# Controller_2_3_Atmega2560.net
KiCad netlist of a schematic drawn in EAGLE
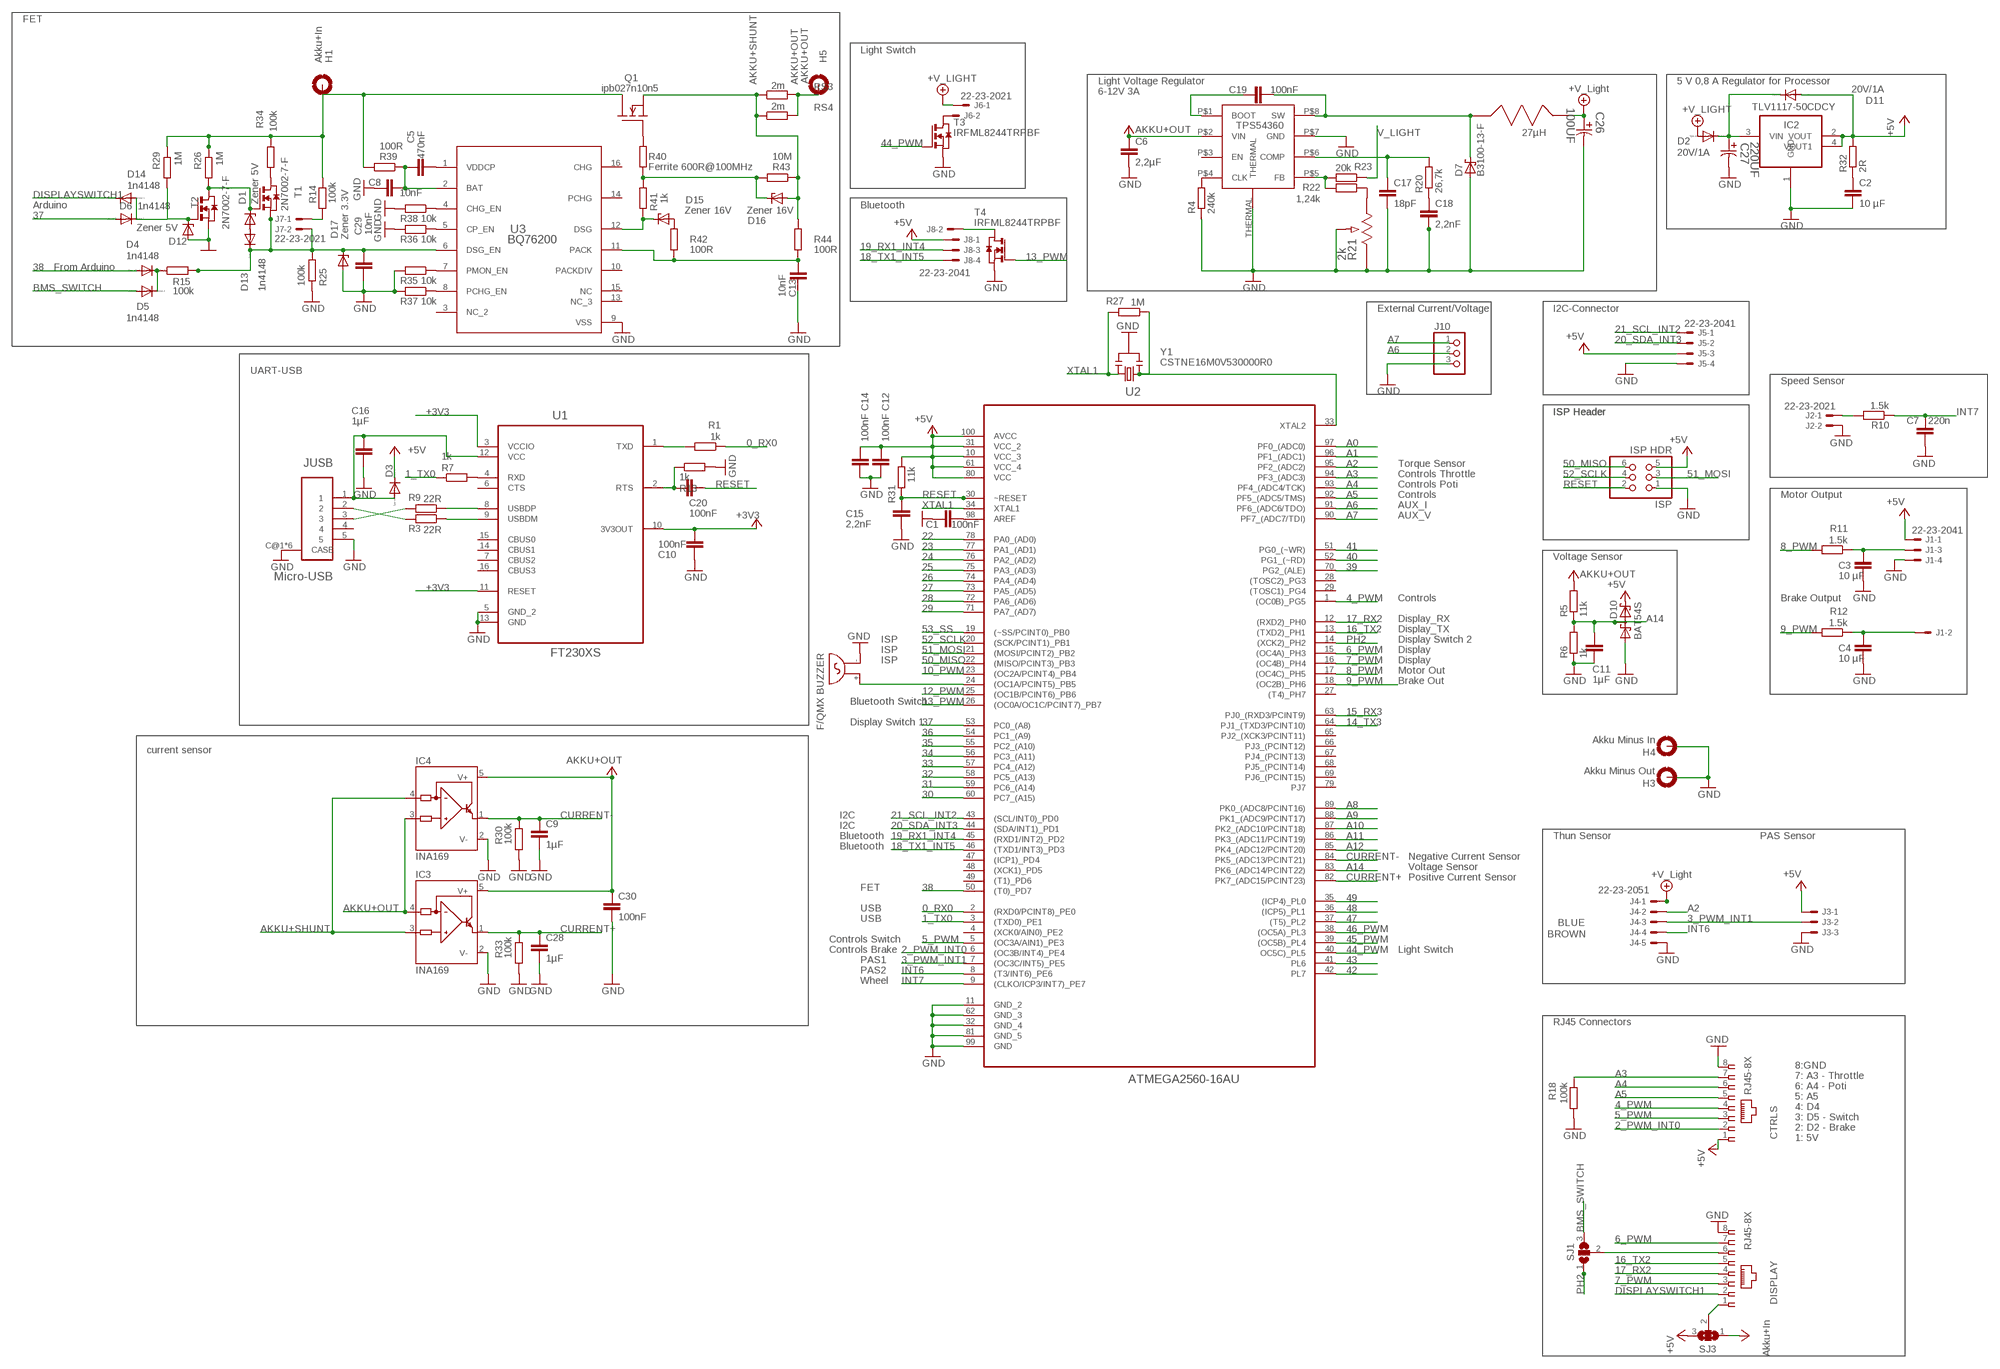
[diagram p0: schematic, sheet 1]

(export (version "E")
  (design (tool "Eeschema 10.0.6"))
  (components
    (comp (ref "BUZZER")
      (value "F/QMX")
      (footprint "eagle-import:F_QMX")
      (libsource (lib "eagle-import") (part "F/QMX"))
    )
    (comp (ref "C1")
      (value "100nF")
      (footprint "eagle-import:C0603")
      (libsource (lib "eagle-import") (part "C-EUC0603"))
    )
    (comp (ref "C2")
      (value "10 µF")
      (footprint "eagle-import:C1206")
      (libsource (lib "eagle-import") (part "C-EUC1206"))
    )
    (comp (ref "C3")
      (value "10 µF")
      (footprint "eagle-import:C1206")
      (libsource (lib "eagle-import") (part "C-EUC1206"))
    )
    (comp (ref "C4")
      (value "10 µF")
      (footprint "eagle-import:C1206")
      (libsource (lib "eagle-import") (part "C-EUC1206"))
    )
    (comp (ref "C5")
      (value "470nF")
      (footprint "eagle-import:C0603")
      (libsource (lib "eagle-import") (part "C-EUC0603"))
    )
    (comp (ref "C6")
      (value "2,2µF")
      (footprint "eagle-import:C1210")
      (libsource (lib "eagle-import") (part "C-EUC1210"))
    )
    (comp (ref "C7")
      (value "220n")
      (footprint "eagle-import:C0603")
      (libsource (lib "eagle-import") (part "C-EUC0603"))
    )
    (comp (ref "C8")
      (value "10nF")
      (footprint "eagle-import:C0603")
      (libsource (lib "eagle-import") (part "C-EUC0603"))
    )
    (comp (ref "C9")
      (value "1µF")
      (footprint "eagle-import:C0603")
      (libsource (lib "eagle-import") (part "C-EUC0603"))
    )
    (comp (ref "C10")
      (value "100nF")
      (footprint "eagle-import:C0603")
      (libsource (lib "eagle-import") (part "C-EUC0603"))
    )
    (comp (ref "C11")
      (value "1µF")
      (footprint "eagle-import:C0603")
      (libsource (lib "eagle-import") (part "C-EUC0603"))
    )
    (comp (ref "C12")
      (value "100nF")
      (footprint "eagle-import:C0603")
      (libsource (lib "eagle-import") (part "C-EUC0603"))
    )
    (comp (ref "C13")
      (value "10nF")
      (footprint "eagle-import:C0603")
      (libsource (lib "eagle-import") (part "C-EUC0603"))
    )
    (comp (ref "C14")
      (value "100nF")
      (footprint "eagle-import:C0603")
      (libsource (lib "eagle-import") (part "C-EUC0603"))
    )
    (comp (ref "C15")
      (value "2,2nF")
      (footprint "eagle-import:C0603")
      (libsource (lib "eagle-import") (part "C-EUC0603"))
    )
    (comp (ref "C16")
      (value "1µF")
      (footprint "eagle-import:C0603")
      (libsource (lib "eagle-import") (part "C-EUC0603"))
    )
    (comp (ref "C17")
      (value "18pF")
      (footprint "eagle-import:C0603")
      (libsource (lib "eagle-import") (part "C-EUC0603"))
    )
    (comp (ref "C18")
      (value "2,2nF")
      (footprint "eagle-import:C0603")
      (libsource (lib "eagle-import") (part "C-EUC0603"))
    )
    (comp (ref "C19")
      (value "100nF")
      (footprint "eagle-import:C0603")
      (libsource (lib "eagle-import") (part "C-EUC0603"))
    )
    (comp (ref "C20")
      (value "100nF")
      (footprint "eagle-import:C0603")
      (libsource (lib "eagle-import") (part "C-EUC0603"))
    )
    (comp (ref "C26")
      (value "100UF")
      (footprint "eagle-import:CAPAE660X800N")
      (fields (field (name "MPN") "EEE-FPE101XAP") (field (name "TOLERANCE") "±20 %"))
      (libsource (lib "eagle-import") (part "EEE--CASE-D8FPE101XAP"))
    )
    (comp (ref "C27")
      (value "220UF")
      (footprint "eagle-import:CAPAE660X800N")
      (fields (field (name "MPN") "EEE-FPC221XAP") (field (name "TOLERANCE") "±20 %"))
      (libsource (lib "eagle-import") (part "EEE--CASE-D8FPC221XAP"))
    )
    (comp (ref "C28")
      (value "1µF")
      (footprint "eagle-import:C0603")
      (libsource (lib "eagle-import") (part "C-EUC0603"))
    )
    (comp (ref "C29")
      (value "10nF")
      (footprint "eagle-import:C0603")
      (libsource (lib "eagle-import") (part "C-EUC0603"))
    )
    (comp (ref "C30")
      (value "100nF")
      (footprint "eagle-import:C0603")
      (libsource (lib "eagle-import") (part "C-EUC0603"))
    )
    (comp (ref "CTRLS")
      (value "RJ45-8X")
      (footprint "eagle-import:RJ45-NO-SHIELD")
      (libsource (lib "eagle-import") (part "RJ45-8X"))
    )
    (comp (ref "D1")
      (value "Zener 5V")
      (footprint "eagle-import:SOD323-W")
      (libsource (lib "eagle-import") (part "ZENER-DIODESOD323-W"))
    )
    (comp (ref "D2")
      (value "20V/1A")
      (footprint "eagle-import:DO-214AC")
      (libsource (lib "eagle-import") (part "DIODE-DO-214AC"))
    )
    (comp (ref "D3")
      (value "20V/1A")
      (footprint "eagle-import:DO-214AC")
      (libsource (lib "eagle-import") (part "DIODE-DO-214AC"))
    )
    (comp (ref "D4")
      (value "1n4148")
      (footprint "eagle-import:SOD323-W")
      (libsource (lib "eagle-import") (part "DIODE-SOD323-W"))
    )
    (comp (ref "D5")
      (value "1n4148")
      (footprint "eagle-import:SOD323-W")
      (libsource (lib "eagle-import") (part "DIODE-SOD323-W"))
    )
    (comp (ref "D6")
      (value "1n4148")
      (footprint "eagle-import:SOD323-W")
      (libsource (lib "eagle-import") (part "DIODE-SOD323-W"))
    )
    (comp (ref "D7")
      (value "B3100-13-F")
      (footprint "eagle-import:SMC")
      (libsource (lib "eagle-import") (part "SCHOTTKY-DIODESMC"))
    )
    (comp (ref "D10")
      (value "BAT54S")
      (footprint "eagle-import:SOT23")
      (libsource (lib "eagle-import") (part "BAT54S"))
    )
    (comp (ref "D11")
      (value "20V/1A")
      (footprint "eagle-import:DO-214AC")
      (libsource (lib "eagle-import") (part "DIODE-DO-214AC"))
    )
    (comp (ref "D12")
      (value "Zener 5V")
      (footprint "eagle-import:SOD323-W")
      (libsource (lib "eagle-import") (part "ZENER-DIODESOD323-W"))
    )
    (comp (ref "D13")
      (value "1n4148")
      (footprint "eagle-import:SOD323-W")
      (libsource (lib "eagle-import") (part "DIODE-SOD323-W"))
    )
    (comp (ref "D14")
      (value "1n4148")
      (footprint "eagle-import:SOD323-W")
      (libsource (lib "eagle-import") (part "DIODE-SOD323-W"))
    )
    (comp (ref "D15")
      (value "Zener 16V")
      (footprint "eagle-import:SOD323-W")
      (libsource (lib "eagle-import") (part "ZENER-DIODESOD323-W"))
    )
    (comp (ref "D16")
      (value "Zener 16V")
      (footprint "eagle-import:SOD323-W")
      (libsource (lib "eagle-import") (part "ZENER-DIODESOD323-W"))
    )
    (comp (ref "D17")
      (value "Zener 3.3V")
      (footprint "eagle-import:SOD323-W")
      (libsource (lib "eagle-import") (part "ZENER-DIODESOD323-W"))
    )
    (comp (ref "DISPLAY")
      (value "RJ45-8X")
      (footprint "eagle-import:RJ45-NO-SHIELD")
      (libsource (lib "eagle-import") (part "RJ45-8X"))
    )
    (comp (ref "H1")
      (value "Akku+In")
      (footprint "eagle-import:2,8-PAD")
      (libsource (lib "eagle-import") (part "MOUNT-PAD-ROUND2.8"))
    )
    (comp (ref "H3")
      (value "Akku Minus Out")
      (footprint "eagle-import:2,8-PAD")
      (libsource (lib "eagle-import") (part "MOUNT-PAD-ROUND2.8"))
    )
    (comp (ref "H4")
      (value "Akku Minus In")
      (footprint "eagle-import:2,8-PAD")
      (libsource (lib "eagle-import") (part "MOUNT-PAD-ROUND2.8"))
    )
    (comp (ref "H5")
      (value "AKKU+OUT")
      (footprint "eagle-import:2,8-PAD")
      (libsource (lib "eagle-import") (part "MOUNT-PAD-ROUND2.8"))
    )
    (comp (ref "IC2")
      (value "TLV1117-50CDCY")
      (footprint "eagle-import:SOT223")
      (fields (field (name "MPN") "REG1117"))
      (libsource (lib "eagle-import") (part "REG1117"))
    )
    (comp (ref "IC3")
      (value "INA169")
      (footprint "eagle-import:SOT23-5")
      (fields (field (name "MF") "TEXAS INSTRUMENTS") (field (name "MPN") "INA168NA/250"))
      (libsource (lib "eagle-import") (part "INA168"))
    )
    (comp (ref "IC4")
      (value "INA169")
      (footprint "eagle-import:SOT23-5")
      (fields (field (name "MF") "TEXAS INSTRUMENTS") (field (name "MPN") "INA168NA/250"))
      (libsource (lib "eagle-import") (part "INA168"))
    )
    (comp (ref "ISP")
      (value "ISP HDR")
      (footprint "eagle-import:2X03")
      (libsource (lib "eagle-import") (part "PINHD-2X3"))
    )
    (comp (ref "J1")
      (value "22-23-2041")
      (footprint "eagle-import:22-23-2041")
      (fields
        (field (name "MF") "MOLEX")
        (field (name "MPN") "22-23-2041")
        (field (name "OC_FARNELL") "1462920")
        (field (name "OC_NEWARK") "38C0355")
      )
      (libsource (lib "eagle-import") (part "22-23-2041"))
    )
    (comp (ref "J2")
      (value "22-23-2021")
      (footprint "eagle-import:22-23-2021")
      (fields (field (name "MF") "MOLEX"))
      (libsource (lib "eagle-import") (part "22-23-2021"))
    )
    (comp (ref "J3")
      (value "22-23-2031")
      (footprint "eagle-import:22-23-2031")
      (fields (field (name "MF") "MOLEX"))
      (libsource (lib "eagle-import") (part "22-23-2031"))
    )
    (comp (ref "J4")
      (value "22-23-2051")
      (footprint "eagle-import:22-23-2051")
      (fields (field (name "MF") "MOLEX"))
      (libsource (lib "eagle-import") (part "22-23-2051"))
    )
    (comp (ref "J5")
      (value "22-23-2041")
      (footprint "eagle-import:22-23-2041")
      (fields (field (name "MF") "MOLEX"))
      (libsource (lib "eagle-import") (part "22-23-2041"))
    )
    (comp (ref "J6")
      (value "22-23-2021")
      (footprint "eagle-import:22-23-2021")
      (fields
        (field (name "MF") "MOLEX")
        (field (name "MF_1") "MOLEX")
        (field (name "MPN") "22-23-2021")
        (field (name "OC_FARNELL") "1462926")
        (field (name "OC_NEWARK") "25C3832")
      )
      (libsource (lib "eagle-import") (part "22-23-2021"))
    )
    (comp (ref "J7")
      (value "22-23-2021")
      (footprint "eagle-import:22-23-2021")
      (fields (field (name "MF") "MOLEX"))
      (libsource (lib "eagle-import") (part "22-23-2021"))
    )
    (comp (ref "J8")
      (value "22-23-2041")
      (footprint "eagle-import:22-23-2041")
      (fields (field (name "MF") "MOLEX"))
      (libsource (lib "eagle-import") (part "22-23-2041"))
    )
    (comp (ref "J10")
      (value "PINHD-1X3")
      (footprint "eagle-import:1X03")
      (libsource (lib "eagle-import") (part "PINHD-1X3"))
    )
    (comp (ref "JUSB")
      (value "Micro-USB")
      (footprint "eagle-import:MOLEX_47346-0001")
      (fields (field (name "MPN") "47346-0001"))
      (libsource (lib "eagle-import") (part "47346-0001"))
    )
    (comp (ref "Q1")
      (value "ipb027n10n5")
      (footprint "eagle-import:D2PAK")
      (libsource (lib "eagle-import") (part "IRF510D2PAK"))
    )
    (comp (ref "R1")
      (value "1k")
      (footprint "eagle-import:R0603")
      (libsource (lib "eagle-import") (part "R-EU_R0603"))
    )
    (comp (ref "R3")
      (value "22R")
      (footprint "eagle-import:R0603")
      (libsource (lib "eagle-import") (part "R-EU_R0603"))
    )
    (comp (ref "R4")
      (value "240k")
      (footprint "eagle-import:R0603")
      (libsource (lib "eagle-import") (part "R-EU_R0603"))
    )
    (comp (ref "R5")
      (value "11k")
      (footprint "eagle-import:R0603")
      (libsource (lib "eagle-import") (part "resistor_R-EU_R0603"))
    )
    (comp (ref "R6")
      (value "1k")
      (footprint "eagle-import:R0603")
      (libsource (lib "eagle-import") (part "resistor_R-EU_R0603"))
    )
    (comp (ref "R7")
      (value "1k")
      (footprint "eagle-import:R0603")
      (libsource (lib "eagle-import") (part "R-EU_R0603"))
    )
    (comp (ref "R9")
      (value "22R")
      (footprint "eagle-import:R0603")
      (libsource (lib "eagle-import") (part "R-EU_R0603"))
    )
    (comp (ref "R10")
      (value "1.5k")
      (footprint "eagle-import:R0603")
      (libsource (lib "eagle-import") (part "R-EU_R0603"))
    )
    (comp (ref "R11")
      (value "1.5k")
      (footprint "eagle-import:R0603")
      (libsource (lib "eagle-import") (part "R-EU_R0603"))
    )
    (comp (ref "R12")
      (value "1.5k")
      (footprint "eagle-import:R0603")
      (libsource (lib "eagle-import") (part "R-EU_R0603"))
    )
    (comp (ref "R13")
      (value "1k")
      (footprint "eagle-import:R0603")
      (libsource (lib "eagle-import") (part "R-EU_R0603"))
    )
    (comp (ref "R14")
      (value "100k")
      (footprint "eagle-import:R0603")
      (libsource (lib "eagle-import") (part "R-EU_R0603"))
    )
    (comp (ref "R15")
      (value "100k")
      (footprint "eagle-import:R0603")
      (libsource (lib "eagle-import") (part "R-EU_R0603"))
    )
    (comp (ref "R18")
      (value "100k")
      (footprint "eagle-import:R0603")
      (libsource (lib "eagle-import") (part "R-EU_R0603"))
    )
    (comp (ref "R20")
      (value "26,7k")
      (footprint "eagle-import:R0603")
      (libsource (lib "eagle-import") (part "R-EU_R0603"))
    )
    (comp (ref "R21")
      (value "2k")
      (footprint "eagle-import:POT_EVM3W")
      (fields (field (name "MPN") "EVM3WSX80B23") (field (name "TOLERANCE") "±25 %"))
      (libsource (lib "eagle-import") (part "EVM-3W3WSX80B23"))
    )
    (comp (ref "R22")
      (value "1,24k")
      (footprint "eagle-import:R0603")
      (libsource (lib "eagle-import") (part "R-EU_R0603"))
    )
    (comp (ref "R23")
      (value "20k")
      (footprint "eagle-import:R0603")
      (libsource (lib "eagle-import") (part "R-EU_R0603"))
    )
    (comp (ref "R25")
      (value "100k")
      (footprint "eagle-import:R0603")
      (libsource (lib "eagle-import") (part "R-EU_R0603"))
    )
    (comp (ref "R26")
      (value "1M")
      (footprint "eagle-import:R0603")
      (libsource (lib "eagle-import") (part "R-EU_R0603"))
    )
    (comp (ref "R27")
      (value "1M")
      (footprint "eagle-import:R0603")
      (libsource (lib "eagle-import") (part "resistor_R-EU_R0603"))
    )
    (comp (ref "R29")
      (value "1M")
      (footprint "eagle-import:R0603")
      (libsource (lib "eagle-import") (part "R-EU_R0603"))
    )
    (comp (ref "R30")
      (value "100k")
      (footprint "eagle-import:R0603")
      (libsource (lib "eagle-import") (part "R-EU_R0603"))
    )
    (comp (ref "R31")
      (value "11k")
      (footprint "eagle-import:R0603")
      (libsource (lib "eagle-import") (part "resistor_R-EU_R0603"))
    )
    (comp (ref "R32")
      (value "2R")
      (footprint "eagle-import:R0603")
      (libsource (lib "eagle-import") (part "R-EU_R0603"))
    )
    (comp (ref "R33")
      (value "100k")
      (footprint "eagle-import:R0603")
      (libsource (lib "eagle-import") (part "R-EU_R0603"))
    )
    (comp (ref "R34")
      (value "100k")
      (footprint "eagle-import:R0603")
      (libsource (lib "eagle-import") (part "R-EU_R0603"))
    )
    (comp (ref "R35")
      (value "10k")
      (footprint "eagle-import:R0603")
      (libsource (lib "eagle-import") (part "R-EU_R0603"))
    )
    (comp (ref "R36")
      (value "10k")
      (footprint "eagle-import:R0603")
      (libsource (lib "eagle-import") (part "R-EU_R0603"))
    )
    (comp (ref "R37")
      (value "10k")
      (footprint "eagle-import:R0603")
      (libsource (lib "eagle-import") (part "R-EU_R0603"))
    )
    (comp (ref "R38")
      (value "10k")
      (footprint "eagle-import:R0603")
      (libsource (lib "eagle-import") (part "R-EU_R0603"))
    )
    (comp (ref "R39")
      (value "100R")
      (footprint "eagle-import:R0603")
      (libsource (lib "eagle-import") (part "R-EU_R0603"))
    )
    (comp (ref "R40")
      (value "Ferrite 600R@100MHz")
      (footprint "eagle-import:R0603")
      (libsource (lib "eagle-import") (part "R-EU_R0603"))
    )
    (comp (ref "R41")
      (value "1k")
      (footprint "eagle-import:R0603")
      (libsource (lib "eagle-import") (part "R-EU_R0603"))
    )
    (comp (ref "R42")
      (value "100R")
      (footprint "eagle-import:R0603")
      (libsource (lib "eagle-import") (part "R-EU_R0603"))
    )
    (comp (ref "R43")
      (value "10M")
      (footprint "eagle-import:R0603")
      (libsource (lib "eagle-import") (part "R-EU_R0603"))
    )
    (comp (ref "R44")
      (value "100R")
      (footprint "eagle-import:R0603")
      (libsource (lib "eagle-import") (part "R-EU_R0603"))
    )
    (comp (ref "RS3")
      (value "2m")
      (footprint "eagle-import:R2512")
      (libsource (lib "eagle-import") (part "R-EU_R2512"))
    )
    (comp (ref "RS4")
      (value "2m")
      (footprint "eagle-import:R2512")
      (libsource (lib "eagle-import") (part "R-EU_R2512"))
    )
    (comp (ref "SJ1")
      (value "SJ2W")
      (footprint "eagle-import:SJ_2")
      (libsource (lib "eagle-import") (part "SJ2W"))
    )
    (comp (ref "SJ3")
      (value "SJ2W")
      (footprint "eagle-import:SJ_2")
      (libsource (lib "eagle-import") (part "SJ2W"))
    )
    (comp (ref "T1")
      (value "2N7002-7-F")
      (footprint "eagle-import:SOT-23")
      (libsource (lib "eagle-import") (part "NMOSSOT23"))
    )
    (comp (ref "T2")
      (value "2N7002-7-F")
      (footprint "eagle-import:SOT-23")
      (libsource (lib "eagle-import") (part "NMOSSOT23"))
    )
    (comp (ref "T3")
      (value "IRFML8244TRPBF")
      (footprint "eagle-import:SOT-23")
      (libsource (lib "eagle-import") (part "NMOSSOT23"))
    )
    (comp (ref "T4")
      (value "IRFML8244TRPBF")
      (footprint "eagle-import:SOT-23")
      (libsource (lib "eagle-import") (part "NMOSSOT23"))
    )
    (comp (ref "U1")
      (value "FT230XS")
      (footprint "eagle-import:SOP63P600X175-16N")
      (libsource (lib "eagle-import") (part "FT230XS"))
    )
    (comp (ref "U2")
      (value "ATMEGA2560-16AU")
      (footprint "eagle-import:QFP50P1600X1600X120-100N")
      (libsource (lib "eagle-import") (part "ATMEGA2560-16AU"))
    )
    (comp (ref "U3")
      (value "BQ76200")
      (footprint "eagle-import:PW0016A_N")
      (fields
        (field (name "ALTERNATEPARTNUMBER") "BQ76200PW")
        (field (name "MANUFACTURER") "Texas Instruments")
        (field (name "PARTNUMBER") "BQ76200PWR")
      )
      (libsource (lib "eagle-import") (part "BQ76200PWR"))
    )
    (comp (ref "U9")
      (value "SRR1260-270M")
      (footprint "eagle-import:ARR1260")
      (libsource (lib "eagle-import") (part "SRR1260-270M"))
    )
    (comp (ref "U11")
      (value "TPS54360")
      (footprint "eagle-import:R-PDSO-G8")
      (libsource (lib "eagle-import") (part "TPS54360"))
    )
    (comp (ref "Y1")
      (value "CSTNE16M0V530000R0")
      (footprint "eagle-import:RESONATOR")
      (libsource (lib "eagle-import") (part "RESONATORMU"))
    )
  )
  (nets
    (net (code "1") (name "+3V3") (class "Default")
      (node (ref "C10") (pin "2") (pinfunction "2_2") (pintype "passive"))
      (node (ref "U1") (pin "10") (pinfunction "3V3OUT_10") (pintype "output"))
      (node (ref "U1") (pin "11") (pinfunction "RESET_11") (pintype "input"))
      (node (ref "U1") (pin "3") (pinfunction "VCCIO_3") (pintype "power_in"))
    )
    (net (code "2") (name "+5V") (class "Default")
      (node (ref "C12") (pin "2") (pinfunction "2_2") (pintype "passive"))
      (node (ref "C14") (pin "2") (pinfunction "2_2") (pintype "passive"))
      (node (ref "CTRLS") (pin "1") (pinfunction "1_1") (pintype "passive"))
      (node (ref "D10") (pin "2") (pinfunction "C2_2") (pintype "passive"))
      (node (ref "D11") (pin "A") (pinfunction "A_A") (pintype "passive"))
      (node (ref "D3") (pin "C") (pinfunction "C_C") (pintype "passive"))
      (node (ref "IC2") (pin "2") (pinfunction "VOUT_2") (pintype "output"))
      (node (ref "IC2") (pin "4") (pinfunction "VOUT1_4") (pintype "output"))
      (node (ref "ISP") (pin "5") (pinfunction "5_5") (pintype "passive"))
      (node (ref "J1") (pin "1") (pinfunction "S_1") (pintype "passive"))
      (node (ref "J3") (pin "1") (pinfunction "S_1") (pintype "passive"))
      (node (ref "J5") (pin "3") (pinfunction "S_3") (pintype "passive"))
      (node (ref "J8") (pin "1") (pinfunction "S_1") (pintype "passive"))
      (node (ref "R31") (pin "2") (pinfunction "2_2") (pintype "passive"))
      (node (ref "R32") (pin "2") (pinfunction "2_2") (pintype "passive"))
      (node (ref "SJ3") (pin "3") (pinfunction "3_3") (pintype "passive"))
      (node (ref "U2") (pin "10") (pinfunction "VCC_3_10") (pintype "power_in"))
      (node (ref "U2") (pin "100") (pinfunction "AVCC_100") (pintype "power_in"))
      (node (ref "U2") (pin "31") (pinfunction "VCC_2_31") (pintype "power_in"))
      (node (ref "U2") (pin "61") (pinfunction "VCC_4_61") (pintype "power_in"))
      (node (ref "U2") (pin "80") (pinfunction "VCC_80") (pintype "power_in"))
    )
    (net (code "3") (name "+V_LIGHT") (class "Default")
      (node (ref "C26") (pin "1") (pinfunction "1_1") (pintype "passive"))
      (node (ref "D2") (pin "A") (pinfunction "A_A") (pintype "passive"))
      (node (ref "J4") (pin "1") (pinfunction "S_1") (pintype "passive"))
      (node (ref "J6") (pin "1") (pinfunction "S_1") (pintype "passive"))
      (node (ref "R23") (pin "1") (pinfunction "1_1") (pintype "passive"))
      (node (ref "U9") (pin "P$2") (pinfunction "P$2_P$2") (pintype "bidirectional"))
    )
    (net (code "4") (name "/0_RX0") (class "Default")
      (node (ref "R1") (pin "1") (pinfunction "1_1") (pintype "passive"))
      (node (ref "U2") (pin "2") (pinfunction "(RXD0/PCINT8)_PE0_2") (pintype "bidirectional"))
    )
    (net (code "5") (name "/1_TX0") (class "Default")
      (node (ref "R7") (pin "1") (pinfunction "1_1") (pintype "passive"))
      (node (ref "U2") (pin "3") (pinfunction "(TXD0)_PE1_3") (pintype "bidirectional"))
    )
    (net (code "6") (name "/2_PWM_INT0") (class "Default")
      (node (ref "CTRLS") (pin "2") (pinfunction "2_2") (pintype "passive"))
      (node (ref "U2") (pin "6") (pinfunction "(OC3B/INT4)_PE4_6") (pintype "bidirectional"))
    )
    (net (code "7") (name "/3_PWM_INT1") (class "Default")
      (node (ref "J3") (pin "2") (pinfunction "S_2") (pintype "passive"))
      (node (ref "J4") (pin "3") (pinfunction "S_3") (pintype "passive"))
      (node (ref "U2") (pin "7") (pinfunction "(OC3C/INT5)_PE5_7") (pintype "bidirectional"))
    )
    (net (code "8") (name "/4_PWM") (class "Default")
      (node (ref "CTRLS") (pin "4") (pinfunction "4_4") (pintype "passive"))
      (node (ref "U2") (pin "1") (pinfunction "(OC0B)_PG5_1") (pintype "bidirectional"))
    )
    (net (code "9") (name "/5_PWM") (class "Default")
      (node (ref "CTRLS") (pin "3") (pinfunction "3_3") (pintype "passive"))
      (node (ref "U2") (pin "5") (pinfunction "(OC3A/AIN1)_PE3_5") (pintype "bidirectional"))
    )
    (net (code "10") (name "/6_PWM") (class "Default")
      (node (ref "DISPLAY") (pin "7") (pinfunction "7_7") (pintype "passive"))
      (node (ref "U2") (pin "15") (pinfunction "(OC4A)_PH3_15") (pintype "bidirectional"))
    )
    (net (code "11") (name "/7_PWM") (class "Default")
      (node (ref "DISPLAY") (pin "3") (pinfunction "3_3") (pintype "passive"))
      (node (ref "U2") (pin "16") (pinfunction "(OC4B)_PH4_16") (pintype "bidirectional"))
    )
    (net (code "12") (name "/8_PWM") (class "Default")
      (node (ref "R11") (pin "2") (pinfunction "2_2") (pintype "passive"))
      (node (ref "U2") (pin "17") (pinfunction "(OC4C)_PH5_17") (pintype "bidirectional"))
    )
    (net (code "13") (name "/9_PWM") (class "Default")
      (node (ref "R12") (pin "2") (pinfunction "2_2") (pintype "passive"))
      (node (ref "U2") (pin "18") (pinfunction "(OC2B)_PH6_18") (pintype "bidirectional"))
    )
    (net (code "14") (name "/10_PWM") (class "Default")
      (node (ref "U2") (pin "23") (pinfunction "(OC2A/PCINT4)_PB4_23") (pintype "bidirectional"))
    )
    (net (code "15") (name "/12_PWM") (class "Default")
      (node (ref "U2") (pin "25") (pinfunction "(OC1B/PCINT6)_PB6_25") (pintype "bidirectional"))
    )
    (net (code "16") (name "/13_PWM") (class "Default")
      (node (ref "T4") (pin "3") (pinfunction "G_3") (pintype "passive"))
      (node (ref "U2") (pin "26") (pinfunction "(OC0A/OC1C/PCINT7)_PB7_26") (pintype "bidirectional"))
    )
    (net (code "17") (name "/14_TX3") (class "Default")
      (node (ref "U2") (pin "64") (pinfunction "PJ1_(TXD3/PCINT10)_64") (pintype "bidirectional"))
    )
    (net (code "18") (name "/15_RX3") (class "Default")
      (node (ref "U2") (pin "63") (pinfunction "PJ0_(RXD3/PCINT9)_63") (pintype "bidirectional"))
    )
    (net (code "19") (name "/16_TX2") (class "Default")
      (node (ref "DISPLAY") (pin "5") (pinfunction "5_5") (pintype "passive"))
      (node (ref "U2") (pin "13") (pinfunction "(TXD2)_PH1_13") (pintype "bidirectional"))
    )
    (net (code "20") (name "/17_RX2") (class "Default")
      (node (ref "DISPLAY") (pin "4") (pinfunction "4_4") (pintype "passive"))
      (node (ref "U2") (pin "12") (pinfunction "(RXD2)_PH0_12") (pintype "bidirectional"))
    )
    (net (code "21") (name "/18_TX1_INT5") (class "Default")
      (node (ref "J8") (pin "4") (pinfunction "S_4") (pintype "passive"))
      (node (ref "U2") (pin "46") (pinfunction "(TXD1/INT3)_PD3_46") (pintype "bidirectional"))
    )
    (net (code "22") (name "/19_RX1_INT4") (class "Default")
      (node (ref "J8") (pin "3") (pinfunction "S_3") (pintype "passive"))
      (node (ref "U2") (pin "45") (pinfunction "(RXD1/INT2)_PD2_45") (pintype "bidirectional"))
    )
    (net (code "23") (name "/20_SDA_INT3") (class "Default")
      (node (ref "J5") (pin "2") (pinfunction "S_2") (pintype "passive"))
      (node (ref "U2") (pin "44") (pinfunction "(SDA/INT1)_PD1_44") (pintype "bidirectional"))
    )
    (net (code "24") (name "/21_SCL_INT2") (class "Default")
      (node (ref "J5") (pin "1") (pinfunction "S_1") (pintype "passive"))
      (node (ref "U2") (pin "43") (pinfunction "(SCL/INT0)_PD0_43") (pintype "bidirectional"))
    )
    (net (code "25") (name "/22") (class "Default")
      (node (ref "U2") (pin "78") (pinfunction "PA0_(AD0)_78") (pintype "bidirectional"))
    )
    (net (code "26") (name "/23") (class "Default")
      (node (ref "U2") (pin "77") (pinfunction "PA1_(AD1)_77") (pintype "bidirectional"))
    )
    (net (code "27") (name "/24") (class "Default")
      (node (ref "U2") (pin "76") (pinfunction "PA2_(AD2)_76") (pintype "bidirectional"))
    )
    (net (code "28") (name "/25") (class "Default")
      (node (ref "U2") (pin "75") (pinfunction "PA3_(AD3)_75") (pintype "bidirectional"))
    )
    (net (code "29") (name "/26") (class "Default")
      (node (ref "U2") (pin "74") (pinfunction "PA4_(AD4)_74") (pintype "bidirectional"))
    )
    (net (code "30") (name "/27") (class "Default")
      (node (ref "U2") (pin "73") (pinfunction "PA5_(AD5)_73") (pintype "bidirectional"))
    )
    (net (code "31") (name "/28") (class "Default")
      (node (ref "U2") (pin "72") (pinfunction "PA6_(AD6)_72") (pintype "bidirectional"))
    )
    (net (code "32") (name "/29") (class "Default")
      (node (ref "U2") (pin "71") (pinfunction "PA7_(AD7)_71") (pintype "bidirectional"))
    )
    (net (code "33") (name "/30") (class "Default")
      (node (ref "U2") (pin "60") (pinfunction "PC7_(A15)_60") (pintype "bidirectional"))
    )
    (net (code "34") (name "/31") (class "Default")
      (node (ref "U2") (pin "59") (pinfunction "PC6_(A14)_59") (pintype "bidirectional"))
    )
    (net (code "35") (name "/32") (class "Default")
      (node (ref "U2") (pin "58") (pinfunction "PC5_(A13)_58") (pintype "bidirectional"))
    )
    (net (code "36") (name "/33") (class "Default")
      (node (ref "U2") (pin "57") (pinfunction "PC4_(A12)_57") (pintype "bidirectional"))
    )
    (net (code "37") (name "/34") (class "Default")
      (node (ref "U2") (pin "56") (pinfunction "PC3_(A11)_56") (pintype "bidirectional"))
    )
    (net (code "38") (name "/35") (class "Default")
      (node (ref "U2") (pin "55") (pinfunction "PC2_(A10)_55") (pintype "bidirectional"))
    )
    (net (code "39") (name "/36") (class "Default")
      (node (ref "U2") (pin "54") (pinfunction "PC1_(A9)_54") (pintype "bidirectional"))
    )
    (net (code "40") (name "/37") (class "Default")
      (node (ref "D6") (pin "A") (pinfunction "A_A") (pintype "passive"))
      (node (ref "U2") (pin "53") (pinfunction "PC0_(A8)_53") (pintype "bidirectional"))
    )
    (net (code "41") (name "/38") (class "Default")
      (node (ref "D4") (pin "A") (pinfunction "A_A") (pintype "passive"))
      (node (ref "U2") (pin "50") (pinfunction "(T0)_PD7_50") (pintype "bidirectional"))
    )
    (net (code "42") (name "/39") (class "Default")
      (node (ref "U2") (pin "70") (pinfunction "PG2_(ALE)_70") (pintype "bidirectional"))
    )
    (net (code "43") (name "/40") (class "Default")
      (node (ref "U2") (pin "52") (pinfunction "PG1_(~{RD})_52") (pintype "bidirectional"))
    )
    (net (code "44") (name "/41") (class "Default")
      (node (ref "U2") (pin "51") (pinfunction "PG0_(~{WR})_51") (pintype "bidirectional"))
    )
    (net (code "45") (name "/42") (class "Default")
      (node (ref "U2") (pin "42") (pinfunction "PL7_42") (pintype "bidirectional"))
    )
    (net (code "46") (name "/43") (class "Default")
      (node (ref "U2") (pin "41") (pinfunction "PL6_41") (pintype "bidirectional"))
    )
    (net (code "47") (name "/44_PWM") (class "Default")
      (node (ref "T3") (pin "3") (pinfunction "G_3") (pintype "passive"))
      (node (ref "U2") (pin "40") (pinfunction "OC5C)_PL5_40") (pintype "bidirectional"))
    )
    (net (code "48") (name "/45_PWM") (class "Default")
      (node (ref "U2") (pin "39") (pinfunction "(OC5B)_PL4_39") (pintype "bidirectional"))
    )
    (net (code "49") (name "/46_PWM") (class "Default")
      (node (ref "U2") (pin "38") (pinfunction "(OC5A)_PL3_38") (pintype "bidirectional"))
    )
    (net (code "50") (name "/47") (class "Default")
      (node (ref "U2") (pin "37") (pinfunction "(T5)_PL2_37") (pintype "bidirectional"))
    )
    (net (code "51") (name "/48") (class "Default")
      (node (ref "U2") (pin "36") (pinfunction "(ICP5)_PL1_36") (pintype "bidirectional"))
    )
    (net (code "52") (name "/49") (class "Default")
      (node (ref "U2") (pin "35") (pinfunction "(ICP4)_PL0_35") (pintype "bidirectional"))
    )
    (net (code "53") (name "/50_MISO") (class "Default")
      (node (ref "ISP") (pin "6") (pinfunction "6_6") (pintype "passive"))
      (node (ref "U2") (pin "22") (pinfunction "(MISO/PCINT3)_PB3_22") (pintype "bidirectional"))
    )
    (net (code "54") (name "/51_MOSI") (class "Default")
      (node (ref "ISP") (pin "3") (pinfunction "3_3") (pintype "passive"))
      (node (ref "U2") (pin "21") (pinfunction "(MOSI/PCINT2)_PB2_21") (pintype "bidirectional"))
    )
    (net (code "55") (name "/52_SCLK") (class "Default")
      (node (ref "ISP") (pin "4") (pinfunction "4_4") (pintype "passive"))
      (node (ref "U2") (pin "20") (pinfunction "(SCK/PCINT1)_PB1_20") (pintype "bidirectional"))
    )
    (net (code "56") (name "/53_SS") (class "Default")
      (node (ref "U2") (pin "19") (pinfunction "(~{SS/PCINT0})_PB0_19") (pintype "bidirectional"))
    )
    (net (code "57") (name "/A0") (class "Default")
      (node (ref "U2") (pin "97") (pinfunction "PF0_(ADC0)_97") (pintype "bidirectional"))
    )
    (net (code "58") (name "/A1") (class "Default")
      (node (ref "U2") (pin "96") (pinfunction "PF1_(ADC1)_96") (pintype "bidirectional"))
    )
    (net (code "59") (name "/A2") (class "Default")
      (node (ref "J4") (pin "2") (pinfunction "S_2") (pintype "passive"))
      (node (ref "U2") (pin "95") (pinfunction "PF2_(ADC2)_95") (pintype "bidirectional"))
    )
    (net (code "60") (name "/A3") (class "Default")
      (node (ref "CTRLS") (pin "7") (pinfunction "7_7") (pintype "passive"))
      (node (ref "R18") (pin "1") (pinfunction "1_1") (pintype "passive"))
      (node (ref "U2") (pin "94") (pinfunction "PF3_(ADC3)_94") (pintype "bidirectional"))
    )
    (net (code "61") (name "/A4") (class "Default")
      (node (ref "CTRLS") (pin "6") (pinfunction "6_6") (pintype "passive"))
      (node (ref "U2") (pin "93") (pinfunction "PF4_(ADC4/TCK)_93") (pintype "bidirectional"))
    )
    (net (code "62") (name "/A5") (class "Default")
      (node (ref "CTRLS") (pin "5") (pinfunction "5_5") (pintype "passive"))
      (node (ref "U2") (pin "92") (pinfunction "PF5_(ADC5/TMS)_92") (pintype "bidirectional"))
    )
    (net (code "63") (name "/A6") (class "Default")
      (node (ref "J10") (pin "2") (pinfunction "2_2") (pintype "passive"))
      (node (ref "U2") (pin "91") (pinfunction "PF6_(ADC6/TDO)_91") (pintype "bidirectional"))
    )
    (net (code "64") (name "/A7") (class "Default")
      (node (ref "J10") (pin "1") (pinfunction "1_1") (pintype "passive"))
      (node (ref "U2") (pin "90") (pinfunction "PF7_(ADC7/TDI)_90") (pintype "bidirectional"))
    )
    (net (code "65") (name "/A8") (class "Default")
      (node (ref "U2") (pin "89") (pinfunction "PK0_(ADC8/PCINT16)_89") (pintype "bidirectional"))
    )
    (net (code "66") (name "/A9") (class "Default")
      (node (ref "U2") (pin "88") (pinfunction "PK1_(ADC9/PCINT17)_88") (pintype "bidirectional"))
    )
    (net (code "67") (name "/A10") (class "Default")
      (node (ref "U2") (pin "87") (pinfunction "PK2_(ADC10/PCINT18)_87") (pintype "bidirectional"))
    )
    (net (code "68") (name "/A11") (class "Default")
      (node (ref "U2") (pin "86") (pinfunction "PK3_(ADC11/PCINT19)_86") (pintype "bidirectional"))
    )
    (net (code "69") (name "/A12") (class "Default")
      (node (ref "U2") (pin "85") (pinfunction "PK4_(ADC12/PCINT20)_85") (pintype "bidirectional"))
    )
    (net (code "70") (name "/A14") (class "Default")
      (node (ref "C11") (pin "1") (pinfunction "1_1") (pintype "passive"))
      (node (ref "D10") (pin "3") (pinfunction "C1A2_3") (pintype "passive"))
      (node (ref "R5") (pin "1") (pinfunction "1_1") (pintype "passive"))
      (node (ref "R6") (pin "2") (pinfunction "2_2") (pintype "passive"))
      (node (ref "U2") (pin "83") (pinfunction "PK6_(ADC14/PCINT22)_83") (pintype "bidirectional"))
    )
    (net (code "71") (name "/AKKU+SHUNT") (class "Default")
      (node (ref "D16") (pin "A") (pinfunction "A_A") (pintype "passive"))
      (node (ref "IC3") (pin "3") (pinfunction "IN+_3") (pintype "input"))
      (node (ref "IC4") (pin "4") (pinfunction "IN-_4") (pintype "input"))
      (node (ref "Q1") (pin "3") (pinfunction "S_3") (pintype "passive"))
      (node (ref "R43") (pin "1") (pinfunction "1_1") (pintype "passive"))
      (node (ref "R44") (pin "2") (pinfunction "2_2") (pintype "passive"))
      (node (ref "RS3") (pin "1") (pinfunction "1_1") (pintype "passive"))
      (node (ref "RS4") (pin "1") (pinfunction "1_1") (pintype "passive"))
    )
    (net (code "72") (name "/BMS_SWITCH") (class "Default")
      (node (ref "D5") (pin "A") (pinfunction "A_A") (pintype "passive"))
      (node (ref "SJ1") (pin "3") (pinfunction "3_3") (pintype "passive"))
    )
    (net (code "73") (name "/CURRENT+") (class "Default")
      (node (ref "C28") (pin "1") (pinfunction "1_1") (pintype "passive"))
      (node (ref "IC3") (pin "1") (pinfunction "OUT_1") (pintype "output"))
      (node (ref "R33") (pin "2") (pinfunction "2_2") (pintype "passive"))
      (node (ref "U2") (pin "82") (pinfunction "PK7_(ADC15/PCINT23)_82") (pintype "bidirectional"))
    )
    (net (code "74") (name "/CURRENT-") (class "Default")
      (node (ref "C9") (pin "1") (pinfunction "1_1") (pintype "passive"))
      (node (ref "IC4") (pin "1") (pinfunction "OUT_1") (pintype "output"))
      (node (ref "R30") (pin "2") (pinfunction "2_2") (pintype "passive"))
      (node (ref "U2") (pin "84") (pinfunction "PK5_(ADC13/PCINT21)_84") (pintype "bidirectional"))
    )
    (net (code "75") (name "/DISPLAYSWITCH1") (class "Default")
      (node (ref "D14") (pin "C") (pinfunction "C_C") (pintype "passive"))
      (node (ref "DISPLAY") (pin "2") (pinfunction "2_2") (pintype "passive"))
    )
    (net (code "76") (name "/INT6") (class "Default")
      (node (ref "J4") (pin "4") (pinfunction "S_4") (pintype "passive"))
      (node (ref "U2") (pin "8") (pinfunction "(T3/INT6)_PE6_8") (pintype "bidirectional"))
    )
    (net (code "77") (name "/INT7") (class "Default")
      (node (ref "C7") (pin "1") (pinfunction "1_1") (pintype "passive"))
      (node (ref "R10") (pin "1") (pinfunction "1_1") (pintype "passive"))
      (node (ref "U2") (pin "9") (pinfunction "(CLKO/ICP3/INT7)_PE7_9") (pintype "bidirectional"))
    )
    (net (code "78") (name "/PH2") (class "Default")
      (node (ref "SJ1") (pin "1") (pinfunction "1_1") (pintype "passive"))
      (node (ref "U2") (pin "14") (pinfunction "(XCK2)_PH2_14") (pintype "bidirectional"))
    )
    (net (code "79") (name "/RESET") (class "Default")
      (node (ref "C15") (pin "1") (pinfunction "1_1") (pintype "passive"))
      (node (ref "C20") (pin "2") (pinfunction "2_2") (pintype "passive"))
      (node (ref "ISP") (pin "2") (pinfunction "2_2") (pintype "passive"))
      (node (ref "R31") (pin "1") (pinfunction "1_1") (pintype "passive"))
      (node (ref "U2") (pin "30") (pinfunction "~{RESET}_30") (pintype "input"))
    )
    (net (code "80") (name "/XTAL1") (class "Default")
      (node (ref "R27") (pin "2") (pinfunction "2_2") (pintype "passive"))
      (node (ref "U2") (pin "34") (pinfunction "XTAL1_34") (pintype "input"))
      (node (ref "Y1") (pin "3") (pinfunction "3_3") (pintype "passive"))
    )
    (net (code "81") (name "AKKU+OUT") (class "Default")
      (node (ref "C30") (pin "1") (pinfunction "1_1") (pintype "passive"))
      (node (ref "C6") (pin "1") (pinfunction "1_1") (pintype "passive"))
      (node (ref "H5") (pin "B2,8") (pinfunction "MOUNT_B2,8") (pintype "passive"))
      (node (ref "IC3") (pin "4") (pinfunction "IN-_4") (pintype "input"))
      (node (ref "IC3") (pin "5") (pinfunction "V+_5") (pintype "power_in"))
      (node (ref "IC4") (pin "3") (pinfunction "IN+_3") (pintype "input"))
      (node (ref "IC4") (pin "5") (pinfunction "V+_5") (pintype "power_in"))
      (node (ref "R5") (pin "2") (pinfunction "2_2") (pintype "passive"))
      (node (ref "RS3") (pin "2") (pinfunction "2_2") (pintype "passive"))
      (node (ref "RS4") (pin "2") (pinfunction "2_2") (pintype "passive"))
      (node (ref "U11") (pin "P$2") (pinfunction "VIN_P$2") (pintype "bidirectional"))
    )
    (net (code "82") (name "Akku+In") (class "Default")
      (node (ref "H1") (pin "B2,8") (pinfunction "MOUNT_B2,8") (pintype "passive"))
      (node (ref "Q1") (pin "2") (pinfunction "D_2") (pintype "passive"))
      (node (ref "R14") (pin "2") (pinfunction "2_2") (pintype "passive"))
      (node (ref "R26") (pin "1") (pinfunction "1_1") (pintype "passive"))
      (node (ref "R29") (pin "1") (pinfunction "1_1") (pintype "passive"))
      (node (ref "R34") (pin "1") (pinfunction "1_1") (pintype "passive"))
      (node (ref "R39") (pin "2") (pinfunction "2_2") (pintype "passive"))
      (node (ref "SJ3") (pin "1") (pinfunction "1_1") (pintype "passive"))
    )
    (net (code "83") (name "GND") (class "Default")
      (node (ref "BUZZER") (pin "-") (pinfunction "1_-") (pintype "passive"))
      (node (ref "C1") (pin "2") (pinfunction "2_2") (pintype "passive"))
      (node (ref "C10") (pin "1") (pinfunction "1_1") (pintype "passive"))
      (node (ref "C11") (pin "2") (pinfunction "2_2") (pintype "passive"))
      (node (ref "C12") (pin "1") (pinfunction "1_1") (pintype "passive"))
      (node (ref "C13") (pin "1") (pinfunction "1_1") (pintype "passive"))
      (node (ref "C14") (pin "1") (pinfunction "1_1") (pintype "passive"))
      (node (ref "C15") (pin "2") (pinfunction "2_2") (pintype "passive"))
      (node (ref "C16") (pin "2") (pinfunction "2_2") (pintype "passive"))
      (node (ref "C17") (pin "2") (pinfunction "2_2") (pintype "passive"))
      (node (ref "C18") (pin "2") (pinfunction "2_2") (pintype "passive"))
      (node (ref "C2") (pin "2") (pinfunction "2_2") (pintype "passive"))
      (node (ref "C26") (pin "2") (pinfunction "2_2") (pintype "passive"))
      (node (ref "C27") (pin "2") (pinfunction "2_2") (pintype "passive"))
      (node (ref "C28") (pin "2") (pinfunction "2_2") (pintype "passive"))
      (node (ref "C29") (pin "1") (pinfunction "1_1") (pintype "passive"))
      (node (ref "C3") (pin "2") (pinfunction "2_2") (pintype "passive"))
      (node (ref "C30") (pin "2") (pinfunction "2_2") (pintype "passive"))
      (node (ref "C4") (pin "2") (pinfunction "2_2") (pintype "passive"))
      (node (ref "C6") (pin "2") (pinfunction "2_2") (pintype "passive"))
      (node (ref "C7") (pin "2") (pinfunction "2_2") (pintype "passive"))
      (node (ref "C8") (pin "1") (pinfunction "1_1") (pintype "passive"))
      (node (ref "C9") (pin "2") (pinfunction "2_2") (pintype "passive"))
      (node (ref "CTRLS") (pin "8") (pinfunction "8_8") (pintype "passive"))
      (node (ref "D10") (pin "1") (pinfunction "A1_1") (pintype "passive"))
      (node (ref "D12") (pin "A") (pinfunction "A_A") (pintype "passive"))
      (node (ref "D17") (pin "A") (pinfunction "A_A") (pintype "passive"))
      (node (ref "D7") (pin "A") (pinfunction "A_A") (pintype "passive"))
      (node (ref "DISPLAY") (pin "8") (pinfunction "8_8") (pintype "passive"))
      (node (ref "H3") (pin "B2,8") (pinfunction "MOUNT_B2,8") (pintype "passive"))
      (node (ref "H4") (pin "B2,8") (pinfunction "MOUNT_B2,8") (pintype "passive"))
      (node (ref "IC2") (pin "1") (pinfunction "GND_1") (pintype "power_in"))
      (node (ref "IC3") (pin "2") (pinfunction "V-_2") (pintype "power_in"))
      (node (ref "IC4") (pin "2") (pinfunction "V-_2") (pintype "power_in"))
      (node (ref "ISP") (pin "1") (pinfunction "1_1") (pintype "passive"))
      (node (ref "J1") (pin "4") (pinfunction "S_4") (pintype "passive"))
      (node (ref "J10") (pin "3") (pinfunction "3_3") (pintype "passive"))
      (node (ref "J2") (pin "2") (pinfunction "S_2") (pintype "passive"))
      (node (ref "J3") (pin "3") (pinfunction "S_3") (pintype "passive"))
      (node (ref "J4") (pin "5") (pinfunction "S_5") (pintype "passive"))
      (node (ref "J5") (pin "4") (pinfunction "S_4") (pintype "passive"))
      (node (ref "JUSB") (pin "5") (pinfunction "5_5") (pintype "input"))
      (node (ref "JUSB") (pin "C@1") (pinfunction "CASE_C@1") (pintype "bidirectional"))
      (node (ref "JUSB") (pin "C@2") (pinfunction "CASE_C@2") (pintype "bidirectional"))
      (node (ref "JUSB") (pin "C@3") (pinfunction "CASE_C@3") (pintype "bidirectional"))
      (node (ref "JUSB") (pin "C@4") (pinfunction "CASE_C@4") (pintype "bidirectional"))
      (node (ref "JUSB") (pin "C@5") (pinfunction "CASE_C@5") (pintype "bidirectional"))
      (node (ref "JUSB") (pin "C@6") (pinfunction "CASE_C@6") (pintype "bidirectional"))
      (node (ref "R13") (pin "2") (pinfunction "2_2") (pintype "passive"))
      (node (ref "R18") (pin "2") (pinfunction "2_2") (pintype "passive"))
      (node (ref "R21") (pin "1") (pinfunction "1_1") (pintype "passive"))
      (node (ref "R21") (pin "2") (pinfunction "2_2") (pintype "passive"))
      (node (ref "R25") (pin "1") (pinfunction "1_1") (pintype "passive"))
      (node (ref "R30") (pin "1") (pinfunction "1_1") (pintype "passive"))
      (node (ref "R33") (pin "1") (pinfunction "1_1") (pintype "passive"))
      (node (ref "R35") (pin "2") (pinfunction "2_2") (pintype "passive"))
      (node (ref "R36") (pin "2") (pinfunction "2_2") (pintype "passive"))
      (node (ref "R37") (pin "2") (pinfunction "2_2") (pintype "passive"))
      (node (ref "R38") (pin "2") (pinfunction "2_2") (pintype "passive"))
      (node (ref "R4") (pin "1") (pinfunction "1_1") (pintype "passive"))
      (node (ref "R6") (pin "1") (pinfunction "1_1") (pintype "passive"))
      (node (ref "T2") (pin "2") (pinfunction "S_2") (pintype "passive"))
      (node (ref "T3") (pin "2") (pinfunction "S_2") (pintype "passive"))
      (node (ref "T4") (pin "2") (pinfunction "S_2") (pintype "passive"))
      (node (ref "U1") (pin "13") (pinfunction "GND_13") (pintype "power_in"))
      (node (ref "U1") (pin "5") (pinfunction "GND_2_5") (pintype "power_in"))
      (node (ref "U11") (pin "P$7") (pinfunction "GND_P$7") (pintype "bidirectional"))
      (node (ref "U11") (pin "THERMAL") (pinfunction "THERMAL_THERMAL") (pintype "bidirectional"))
      (node (ref "U2") (pin "11") (pinfunction "GND_2_11") (pintype "passive"))
      (node (ref "U2") (pin "32") (pinfunction "GND_4_32") (pintype "passive"))
      (node (ref "U2") (pin "62") (pinfunction "GND_3_62") (pintype "passive"))
      (node (ref "U2") (pin "81") (pinfunction "GND_5_81") (pintype "passive"))
      (node (ref "U2") (pin "99") (pinfunction "GND_99") (pintype "passive"))
      (node (ref "U3") (pin "9") (pinfunction "VSS_9") (pintype "power_in"))
      (node (ref "Y1") (pin "2") (pinfunction "2_2") (pintype "passive"))
    )
    (net (code "84") (name "Net-(BUZZER-2)") (class "Default")
      (node (ref "BUZZER") (pin "+") (pinfunction "2_+") (pintype "passive"))
      (node (ref "U2") (pin "24") (pinfunction "(OC1A/PCINT5)_PB5_24") (pintype "bidirectional"))
    )
    (net (code "85") (name "Net-(C2-Pad1)") (class "Default")
      (node (ref "C2") (pin "1") (pinfunction "1_1") (pintype "passive"))
      (node (ref "R32") (pin "1") (pinfunction "1_1") (pintype "passive"))
    )
    (net (code "86") (name "Net-(C18-Pad1)") (class "Default")
      (node (ref "C18") (pin "1") (pinfunction "1_1") (pintype "passive"))
      (node (ref "R20") (pin "1") (pinfunction "1_1") (pintype "passive"))
    )
    (net (code "87") (name "Net-(D1-PadA)") (class "Default")
      (node (ref "D1") (pin "A") (pinfunction "A_A") (pintype "passive"))
      (node (ref "D13") (pin "A") (pinfunction "A_A") (pintype "passive"))
    )
    (net (code "88") (name "Net-(D4-PadC)") (class "Default")
      (node (ref "D4") (pin "C") (pinfunction "C_C") (pintype "passive"))
      (node (ref "D5") (pin "C") (pinfunction "C_C") (pintype "passive"))
      (node (ref "R15") (pin "1") (pinfunction "1_1") (pintype "passive"))
    )
    (net (code "89") (name "Net-(D15-PadA)") (class "Default")
      (node (ref "D15") (pin "A") (pinfunction "A_A") (pintype "passive"))
      (node (ref "R42") (pin "2") (pinfunction "2_2") (pintype "passive"))
    )
    (net (code "90") (name "Net-(D16-PadC)") (class "Default")
      (node (ref "D16") (pin "C") (pinfunction "C_C") (pintype "passive"))
      (node (ref "R40") (pin "1") (pinfunction "1_1") (pintype "passive"))
      (node (ref "R41") (pin "2") (pinfunction "2_2") (pintype "passive"))
      (node (ref "R43") (pin "2") (pinfunction "2_2") (pintype "passive"))
    )
    (net (code "91") (name "Net-(DISPLAY-Pad1)") (class "Default")
      (node (ref "DISPLAY") (pin "1") (pinfunction "1_1") (pintype "passive"))
      (node (ref "SJ3") (pin "2") (pinfunction "2_2") (pintype "passive"))
    )
    (net (code "92") (name "Net-(DISPLAY-Pad6)") (class "Default")
      (node (ref "DISPLAY") (pin "6") (pinfunction "6_6") (pintype "passive"))
      (node (ref "SJ1") (pin "2") (pinfunction "2_2") (pintype "passive"))
    )
    (net (code "93") (name "Net-(IC2-VIN)") (class "Default")
      (node (ref "C27") (pin "1") (pinfunction "1_1") (pintype "passive"))
      (node (ref "D11") (pin "C") (pinfunction "C_C") (pintype "passive"))
      (node (ref "D2") (pin "C") (pinfunction "C_C") (pintype "passive"))
      (node (ref "IC2") (pin "3") (pinfunction "VIN_3") (pintype "input"))
    )
    (net (code "94") (name "Net-(J1B-S)") (class "Default")
      (node (ref "C4") (pin "1") (pinfunction "1_1") (pintype "passive"))
      (node (ref "J1") (pin "2") (pinfunction "S_2") (pintype "passive"))
      (node (ref "R12") (pin "1") (pinfunction "1_1") (pintype "passive"))
    )
    (net (code "95") (name "Net-(J1C-S)") (class "Default")
      (node (ref "C3") (pin "1") (pinfunction "1_1") (pintype "passive"))
      (node (ref "J1") (pin "3") (pinfunction "S_3") (pintype "passive"))
      (node (ref "R11") (pin "1") (pinfunction "1_1") (pintype "passive"))
    )
    (net (code "96") (name "Net-(J2A-S)") (class "Default")
      (node (ref "J2") (pin "1") (pinfunction "S_1") (pintype "passive"))
      (node (ref "R10") (pin "2") (pinfunction "2_2") (pintype "passive"))
    )
    (net (code "97") (name "Net-(J6B-S)") (class "Default")
      (node (ref "J6") (pin "2") (pinfunction "S_2") (pintype "passive"))
      (node (ref "T3") (pin "1") (pinfunction "D_1") (pintype "passive"))
    )
    (net (code "98") (name "Net-(J7A-S)") (class "Default")
      (node (ref "J7") (pin "1") (pinfunction "S_1") (pintype "passive"))
      (node (ref "R14") (pin "1") (pinfunction "1_1") (pintype "passive"))
    )
    (net (code "99") (name "Net-(J7B-S)") (class "Default")
      (node (ref "C29") (pin "2") (pinfunction "2_2") (pintype "passive"))
      (node (ref "D13") (pin "C") (pinfunction "C_C") (pintype "passive"))
      (node (ref "D17") (pin "C") (pinfunction "C_C") (pintype "passive"))
      (node (ref "J7") (pin "2") (pinfunction "S_2") (pintype "passive"))
      (node (ref "R15") (pin "2") (pinfunction "2_2") (pintype "passive"))
      (node (ref "R25") (pin "2") (pinfunction "2_2") (pintype "passive"))
      (node (ref "T1") (pin "2") (pinfunction "S_2") (pintype "passive"))
      (node (ref "U3") (pin "6") (pinfunction "DSG_EN_6") (pintype "input"))
    )
    (net (code "100") (name "Net-(J8B-S)") (class "Default")
      (node (ref "J8") (pin "2") (pinfunction "S_2") (pintype "passive"))
      (node (ref "T4") (pin "1") (pinfunction "D_1") (pintype "passive"))
    )
    (net (code "101") (name "Net-(JUSB-Pad2)") (class "Default")
      (node (ref "JUSB") (pin "2") (pinfunction "2_2") (pintype "input"))
      (node (ref "R3") (pin "2") (pinfunction "2_2") (pintype "passive"))
    )
    (net (code "102") (name "Net-(JUSB-Pad3)") (class "Default")
      (node (ref "JUSB") (pin "3") (pinfunction "3_3") (pintype "input"))
      (node (ref "R9") (pin "2") (pinfunction "2_2") (pintype "passive"))
    )
    (net (code "103") (name "Net-(Q1-G)") (class "Default")
      (node (ref "Q1") (pin "1") (pinfunction "G_1") (pintype "passive"))
      (node (ref "R40") (pin "2") (pinfunction "2_2") (pintype "passive"))
    )
    (net (code "104") (name "Net-(R21-Pad3)") (class "Default")
      (node (ref "R21") (pin "3") (pinfunction "3_3") (pintype "passive"))
      (node (ref "R22") (pin "1") (pinfunction "1_1") (pintype "passive"))
    )
    (net (code "105") (name "Net-(T1-D)") (class "Default")
      (node (ref "R34") (pin "2") (pinfunction "2_2") (pintype "passive"))
      (node (ref "T1") (pin "1") (pinfunction "D_1") (pintype "passive"))
    )
    (net (code "106") (name "Net-(T1-G)") (class "Default")
      (node (ref "D1") (pin "C") (pinfunction "C_C") (pintype "passive"))
      (node (ref "R26") (pin "2") (pinfunction "2_2") (pintype "passive"))
      (node (ref "T1") (pin "3") (pinfunction "G_3") (pintype "passive"))
      (node (ref "T2") (pin "1") (pinfunction "D_1") (pintype "passive"))
    )
    (net (code "107") (name "Net-(T2-G)") (class "Default")
      (node (ref "D12") (pin "C") (pinfunction "C_C") (pintype "passive"))
      (node (ref "D14") (pin "A") (pinfunction "A_A") (pintype "passive"))
      (node (ref "D6") (pin "C") (pinfunction "C_C") (pintype "passive"))
      (node (ref "R29") (pin "2") (pinfunction "2_2") (pintype "passive"))
      (node (ref "T2") (pin "3") (pinfunction "G_3") (pintype "passive"))
    )
    (net (code "108") (name "Net-(U1-RTS)") (class "Default")
      (node (ref "C20") (pin "1") (pinfunction "1_1") (pintype "passive"))
      (node (ref "R13") (pin "1") (pinfunction "1_1") (pintype "passive"))
      (node (ref "U1") (pin "2") (pinfunction "RTS_2") (pintype "output"))
    )
    (net (code "109") (name "Net-(U1-RXD)") (class "Default")
      (node (ref "R7") (pin "2") (pinfunction "2_2") (pintype "passive"))
      (node (ref "U1") (pin "4") (pinfunction "RXD_4") (pintype "input"))
    )
    (net (code "110") (name "Net-(U1-TXD)") (class "Default")
      (node (ref "R1") (pin "2") (pinfunction "2_2") (pintype "passive"))
      (node (ref "U1") (pin "1") (pinfunction "TXD_1") (pintype "output"))
    )
    (net (code "111") (name "Net-(U1-USBDM)") (class "Default")
      (node (ref "R3") (pin "1") (pinfunction "1_1") (pintype "passive"))
      (node (ref "U1") (pin "9") (pinfunction "USBDM_9") (pintype "input"))
    )
    (net (code "112") (name "Net-(U1-USBDP)") (class "Default")
      (node (ref "R9") (pin "1") (pinfunction "1_1") (pintype "passive"))
      (node (ref "U1") (pin "8") (pinfunction "USBDP_8") (pintype "input"))
    )
    (net (code "113") (name "Net-(U1-VCC)") (class "Default")
      (node (ref "C16") (pin "1") (pinfunction "1_1") (pintype "passive"))
      (node (ref "D3") (pin "A") (pinfunction "A_A") (pintype "passive"))
      (node (ref "JUSB") (pin "1") (pinfunction "1_1") (pintype "input"))
      (node (ref "U1") (pin "12") (pinfunction "VCC_12") (pintype "output"))
    )
    (net (code "114") (name "Net-(U2-AREF)") (class "Default")
      (node (ref "C1") (pin "1") (pinfunction "1_1") (pintype "passive"))
      (node (ref "U2") (pin "98") (pinfunction "AREF_98") (pintype "input"))
    )
    (net (code "115") (name "Net-(U2-XTAL2)") (class "Default")
      (node (ref "R27") (pin "1") (pinfunction "1_1") (pintype "passive"))
      (node (ref "U2") (pin "33") (pinfunction "XTAL2_33") (pintype "output"))
      (node (ref "Y1") (pin "1") (pinfunction "1_1") (pintype "passive"))
    )
    (net (code "116") (name "Net-(U3-BAT)") (class "Default")
      (node (ref "C5") (pin "1") (pinfunction "1_1") (pintype "passive"))
      (node (ref "C8") (pin "2") (pinfunction "2_2") (pintype "passive"))
      (node (ref "R39") (pin "1") (pinfunction "1_1") (pintype "passive"))
      (node (ref "U3") (pin "2") (pinfunction "BAT_2") (pintype "power_in"))
    )
    (net (code "117") (name "Net-(U3-CHG_EN)") (class "Default")
      (node (ref "R38") (pin "1") (pinfunction "1_1") (pintype "passive"))
      (node (ref "U3") (pin "4") (pinfunction "CHG_EN_4") (pintype "input"))
    )
    (net (code "118") (name "Net-(U3-CP_EN)") (class "Default")
      (node (ref "R36") (pin "1") (pinfunction "1_1") (pintype "passive"))
      (node (ref "U3") (pin "5") (pinfunction "CP_EN_5") (pintype "input"))
    )
    (net (code "119") (name "Net-(U3-DSG)") (class "Default")
      (node (ref "D15") (pin "C") (pinfunction "C_C") (pintype "passive"))
      (node (ref "R41") (pin "1") (pinfunction "1_1") (pintype "passive"))
      (node (ref "U3") (pin "12") (pinfunction "DSG_12") (pintype "output"))
    )
    (net (code "120") (name "Net-(U3-PACK)") (class "Default")
      (node (ref "C13") (pin "2") (pinfunction "2_2") (pintype "passive"))
      (node (ref "R42") (pin "1") (pinfunction "1_1") (pintype "passive"))
      (node (ref "R44") (pin "1") (pinfunction "1_1") (pintype "passive"))
      (node (ref "U3") (pin "11") (pinfunction "PACK_11") (pintype "power_in"))
    )
    (net (code "121") (name "Net-(U3-PCHG_EN)") (class "Default")
      (node (ref "R37") (pin "1") (pinfunction "1_1") (pintype "passive"))
      (node (ref "U3") (pin "8") (pinfunction "PCHG_EN_8") (pintype "input"))
    )
    (net (code "122") (name "Net-(U3-PMON_EN)") (class "Default")
      (node (ref "R35") (pin "1") (pinfunction "1_1") (pintype "passive"))
      (node (ref "U3") (pin "7") (pinfunction "PMON_EN_7") (pintype "input"))
    )
    (net (code "123") (name "Net-(U3-VDDCP)") (class "Default")
      (node (ref "C5") (pin "2") (pinfunction "2_2") (pintype "passive"))
      (node (ref "U3") (pin "1") (pinfunction "VDDCP_1") (pintype "output"))
    )
    (net (code "124") (name "Net-(U11-BOOT)") (class "Default")
      (node (ref "C19") (pin "1") (pinfunction "1_1") (pintype "passive"))
      (node (ref "U11") (pin "P$1") (pinfunction "BOOT_P$1") (pintype "bidirectional"))
    )
    (net (code "125") (name "Net-(U11-CLK)") (class "Default")
      (node (ref "R4") (pin "2") (pinfunction "2_2") (pintype "passive"))
      (node (ref "U11") (pin "P$4") (pinfunction "CLK_P$4") (pintype "bidirectional"))
    )
    (net (code "126") (name "Net-(U11-COMP)") (class "Default")
      (node (ref "C17") (pin "1") (pinfunction "1_1") (pintype "passive"))
      (node (ref "R20") (pin "2") (pinfunction "2_2") (pintype "passive"))
      (node (ref "U11") (pin "P$6") (pinfunction "COMP_P$6") (pintype "bidirectional"))
    )
    (net (code "127") (name "Net-(U11-FB)") (class "Default")
      (node (ref "R22") (pin "2") (pinfunction "2_2") (pintype "passive"))
      (node (ref "R23") (pin "2") (pinfunction "2_2") (pintype "passive"))
      (node (ref "U11") (pin "P$5") (pinfunction "FB_P$5") (pintype "bidirectional"))
    )
    (net (code "128") (name "Net-(U11-SW)") (class "Default")
      (node (ref "C19") (pin "2") (pinfunction "2_2") (pintype "passive"))
      (node (ref "D7") (pin "C") (pinfunction "C_C") (pintype "passive"))
      (node (ref "U11") (pin "P$8") (pinfunction "SW_P$8") (pintype "bidirectional"))
      (node (ref "U9") (pin "P$1") (pinfunction "P$1_P$1") (pintype "bidirectional"))
    )
    (net (code "129") (name "unconnected-(JUSB-Pad4)") (class "Default")
      (node (ref "JUSB") (pin "4") (pinfunction "4_4") (pintype "input"))
    )
    (net (code "130") (name "unconnected-(U1-CBUS0-Pad15)") (class "Default")
      (node (ref "U1") (pin "15") (pinfunction "CBUS0_15") (pintype "input"))
    )
    (net (code "131") (name "unconnected-(U1-CBUS1-Pad14)") (class "Default")
      (node (ref "U1") (pin "14") (pinfunction "CBUS1_14") (pintype "input"))
    )
    (net (code "132") (name "unconnected-(U1-CBUS2-Pad7)") (class "Default")
      (node (ref "U1") (pin "7") (pinfunction "CBUS2_7") (pintype "input"))
    )
    (net (code "133") (name "unconnected-(U1-CBUS3-Pad16)") (class "Default")
      (node (ref "U1") (pin "16") (pinfunction "CBUS3_16") (pintype "input"))
    )
    (net (code "134") (name "unconnected-(U1-CTS-Pad6)") (class "Default")
      (node (ref "U1") (pin "6") (pinfunction "CTS_6") (pintype "input"))
    )
    (net (code "135") (name "unconnected-(U2-(ICP1)_PD4-Pad47)") (class "Default")
      (node (ref "U2") (pin "47") (pinfunction "(ICP1)_PD4_47") (pintype "bidirectional"))
    )
    (net (code "136") (name "unconnected-(U2-(T1)_PD6-Pad49)") (class "Default")
      (node (ref "U2") (pin "49") (pinfunction "(T1)_PD6_49") (pintype "bidirectional"))
    )
    (net (code "137") (name "unconnected-(U2-(T4)_PH7-Pad27)") (class "Default")
      (node (ref "U2") (pin "27") (pinfunction "(T4)_PH7_27") (pintype "bidirectional"))
    )
    (net (code "138") (name "unconnected-(U2-(TOSC1)_PG4-Pad29)") (class "Default")
      (node (ref "U2") (pin "29") (pinfunction "(TOSC1)_PG4_29") (pintype "bidirectional"))
    )
    (net (code "139") (name "unconnected-(U2-(TOSC2)_PG3-Pad28)") (class "Default")
      (node (ref "U2") (pin "28") (pinfunction "(TOSC2)_PG3_28") (pintype "bidirectional"))
    )
    (net (code "140") (name "unconnected-(U2-(XCK0{slash}AIN0)_PE2-Pad4)") (class "Default")
      (node (ref "U2") (pin "4") (pinfunction "(XCK0/AIN0)_PE2_4") (pintype "bidirectional"))
    )
    (net (code "141") (name "unconnected-(U2-(XCK1)_PD5-Pad48)") (class "Default")
      (node (ref "U2") (pin "48") (pinfunction "(XCK1)_PD5_48") (pintype "bidirectional"))
    )
    (net (code "142") (name "unconnected-(U2-PJ2_(XCK3{slash}PCINT11)-Pad65)") (class "Default")
      (node (ref "U2") (pin "65") (pinfunction "PJ2_(XCK3/PCINT11)_65") (pintype "bidirectional"))
    )
    (net (code "143") (name "unconnected-(U2-PJ3_(PCINT12)-Pad66)") (class "Default")
      (node (ref "U2") (pin "66") (pinfunction "PJ3_(PCINT12)_66") (pintype "bidirectional"))
    )
    (net (code "144") (name "unconnected-(U2-PJ4_(PCINT13)-Pad67)") (class "Default")
      (node (ref "U2") (pin "67") (pinfunction "PJ4_(PCINT13)_67") (pintype "bidirectional"))
    )
    (net (code "145") (name "unconnected-(U2-PJ5_(PCINT14)-Pad68)") (class "Default")
      (node (ref "U2") (pin "68") (pinfunction "PJ5_(PCINT14)_68") (pintype "bidirectional"))
    )
    (net (code "146") (name "unconnected-(U2-PJ6_(PCINT15)-Pad69)") (class "Default")
      (node (ref "U2") (pin "69") (pinfunction "PJ6_(PCINT15)_69") (pintype "bidirectional"))
    )
    (net (code "147") (name "unconnected-(U2-PJ7-Pad79)") (class "Default")
      (node (ref "U2") (pin "79") (pinfunction "PJ7_79") (pintype "bidirectional"))
    )
    (net (code "148") (name "unconnected-(U3-CHG-Pad16)") (class "Default")
      (node (ref "U3") (pin "16") (pinfunction "CHG_16") (pintype "output"))
    )
    (net (code "149") (name "unconnected-(U3-NC-Pad15)") (class "Default")
      (node (ref "U3") (pin "15") (pinfunction "NC_15") (pintype "passive"))
    )
    (net (code "150") (name "unconnected-(U3-NC_2-Pad3)") (class "Default")
      (node (ref "U3") (pin "3") (pinfunction "NC_2_3") (pintype "passive"))
    )
    (net (code "151") (name "unconnected-(U3-NC_3-Pad13)") (class "Default")
      (node (ref "U3") (pin "13") (pinfunction "NC_3_13") (pintype "passive"))
    )
    (net (code "152") (name "unconnected-(U3-PACKDIV-Pad10)") (class "Default")
      (node (ref "U3") (pin "10") (pinfunction "PACKDIV_10") (pintype "output"))
    )
    (net (code "153") (name "unconnected-(U3-PCHG-Pad14)") (class "Default")
      (node (ref "U3") (pin "14") (pinfunction "PCHG_14") (pintype "output"))
    )
    (net (code "154") (name "unconnected-(U11-EN-PadP$3)") (class "Default")
      (node (ref "U11") (pin "P$3") (pinfunction "EN_P$3") (pintype "bidirectional"))
    )
  )
)
